# VideoMacPac_adapter.net
KiCad netlist of a schematic drawn in EAGLE
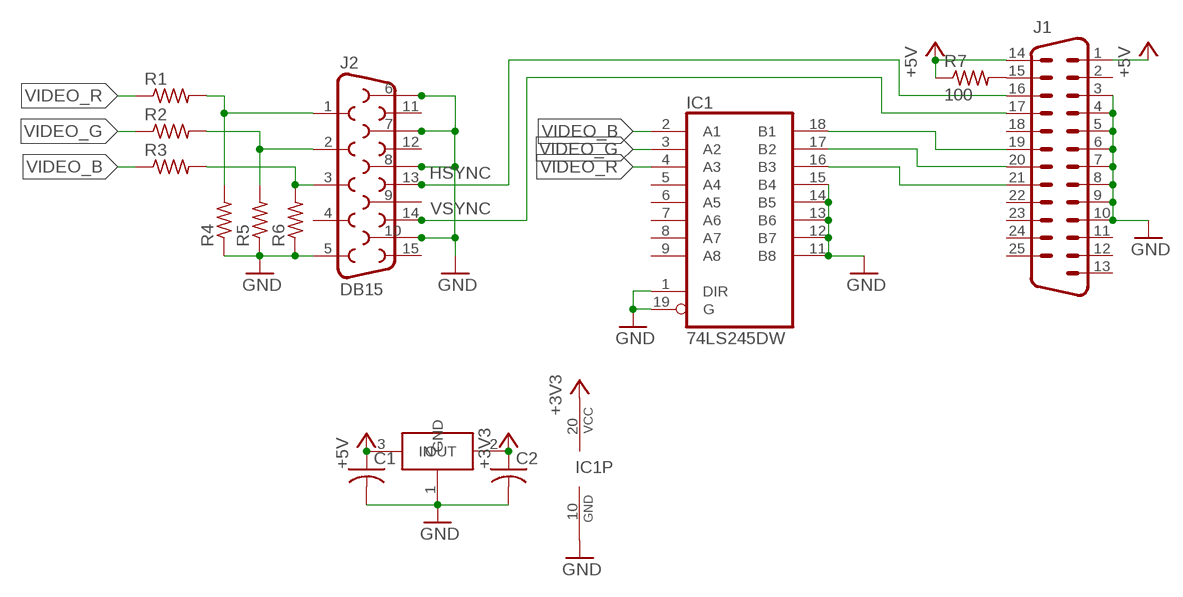
[diagram p0: schematic, sheet 1]

(export (version "E")
  (design (tool "Eeschema 10.0.6"))
  (components
    (comp (ref "C1")
      (value "C-USC0603")
      (footprint "eagle-import:C0603")
      (libsource (lib "eagle-import") (part "C-USC0603"))
    )
    (comp (ref "C2")
      (value "C-USC0603")
      (footprint "eagle-import:C0603")
      (libsource (lib "eagle-import") (part "C-USC0603"))
    )
    (comp (ref "IC1")
      (value "74LS245DW")
      (footprint "eagle-import:SO20W")
      (libsource (lib "eagle-import") (part "74245DWLS"))
    )
    (comp (ref "IC2")
      (value "MCP1700")
      (footprint "eagle-import:SOT23")
      (libsource (lib "eagle-import") (part "MCP1700"))
    )
    (comp (ref "J1")
      (value "DB25H")
      (footprint "eagle-import:M25H")
      (libsource (lib "eagle-import") (part "DB25H"))
    )
    (comp (ref "J2")
      (value "DB15")
      (footprint "eagle-import:DB15")
      (libsource (lib "eagle-import") (part "DB15"))
    )
    (comp (ref "R1")
      (value "R-US_R0603")
      (footprint "eagle-import:R0603")
      (libsource (lib "eagle-import") (part "R-US_R0603"))
    )
    (comp (ref "R2")
      (value "R-US_R0603")
      (footprint "eagle-import:R0603")
      (libsource (lib "eagle-import") (part "R-US_R0603"))
    )
    (comp (ref "R3")
      (value "R-US_R0603")
      (footprint "eagle-import:R0603")
      (libsource (lib "eagle-import") (part "R-US_R0603"))
    )
    (comp (ref "R4")
      (value "R-US_R0603")
      (footprint "eagle-import:R0603")
      (libsource (lib "eagle-import") (part "R-US_R0603"))
    )
    (comp (ref "R5")
      (value "R-US_R0603")
      (footprint "eagle-import:R0603")
      (libsource (lib "eagle-import") (part "R-US_R0603"))
    )
    (comp (ref "R6")
      (value "R-US_R0603")
      (footprint "eagle-import:R0603")
      (libsource (lib "eagle-import") (part "R-US_R0603"))
    )
    (comp (ref "R7")
      (value "100")
      (footprint "eagle-import:R0603")
      (libsource (lib "eagle-import") (part "R-US_R0603"))
    )
  )
  (nets
    (net (code "1") (name "+3V3") (class "Default")
      (node (ref "C2") (pin "1") (pinfunction "1_1") (pintype "passive"))
      (node (ref "IC1") (pin "20") (pinfunction "VCC_20") (pintype "power_in"))
      (node (ref "IC2") (pin "2") (pinfunction "OUT_2") (pintype "bidirectional"))
    )
    (net (code "2") (name "+5V") (class "Default")
      (node (ref "C1") (pin "1") (pinfunction "1_1") (pintype "passive"))
      (node (ref "IC2") (pin "3") (pinfunction "IN_3") (pintype "bidirectional"))
      (node (ref "J1") (pin "1") (pinfunction "1_1") (pintype "passive"))
      (node (ref "J1") (pin "14") (pinfunction "14_14") (pintype "passive"))
      (node (ref "R7") (pin "1") (pinfunction "1_1") (pintype "passive"))
    )
    (net (code "3") (name "/HSYNC") (class "Default")
      (node (ref "J1") (pin "16") (pinfunction "16_16") (pintype "passive"))
      (node (ref "J2") (pin "13") (pinfunction "13_13") (pintype "passive"))
    )
    (net (code "4") (name "/VSYNC") (class "Default")
      (node (ref "J1") (pin "17") (pinfunction "17_17") (pintype "passive"))
      (node (ref "J2") (pin "14") (pinfunction "14_14") (pintype "passive"))
    )
    (net (code "5") (name "GND") (class "Default")
      (node (ref "C1") (pin "2") (pinfunction "2_2") (pintype "passive"))
      (node (ref "C2") (pin "2") (pinfunction "2_2") (pintype "passive"))
      (node (ref "IC1") (pin "1") (pinfunction "DIR_1") (pintype "input"))
      (node (ref "IC1") (pin "10") (pinfunction "GND_10") (pintype "power_in"))
      (node (ref "IC1") (pin "11") (pinfunction "B8_11") (pintype "bidirectional"))
      (node (ref "IC1") (pin "12") (pinfunction "B7_12") (pintype "bidirectional"))
      (node (ref "IC1") (pin "13") (pinfunction "B6_13") (pintype "bidirectional"))
      (node (ref "IC1") (pin "14") (pinfunction "B5_14") (pintype "bidirectional"))
      (node (ref "IC1") (pin "15") (pinfunction "B4_15") (pintype "bidirectional"))
      (node (ref "IC1") (pin "19") (pinfunction "G_19") (pintype "input"))
      (node (ref "IC2") (pin "1") (pinfunction "GND_1") (pintype "bidirectional"))
      (node (ref "J1") (pin "10") (pinfunction "10_10") (pintype "passive"))
      (node (ref "J1") (pin "3") (pinfunction "3_3") (pintype "passive"))
      (node (ref "J1") (pin "4") (pinfunction "4_4") (pintype "passive"))
      (node (ref "J1") (pin "5") (pinfunction "5_5") (pintype "passive"))
      (node (ref "J1") (pin "6") (pinfunction "6_6") (pintype "passive"))
      (node (ref "J1") (pin "7") (pinfunction "7_7") (pintype "passive"))
      (node (ref "J1") (pin "8") (pinfunction "8_8") (pintype "passive"))
      (node (ref "J1") (pin "9") (pinfunction "9_9") (pintype "passive"))
      (node (ref "J2") (pin "10") (pinfunction "10_10") (pintype "passive"))
      (node (ref "J2") (pin "5") (pinfunction "5_5") (pintype "passive"))
      (node (ref "J2") (pin "6") (pinfunction "6_6") (pintype "passive"))
      (node (ref "J2") (pin "7") (pinfunction "7_7") (pintype "passive"))
      (node (ref "J2") (pin "8") (pinfunction "8_8") (pintype "passive"))
      (node (ref "R4") (pin "1") (pinfunction "1_1") (pintype "passive"))
      (node (ref "R5") (pin "1") (pinfunction "1_1") (pintype "passive"))
      (node (ref "R6") (pin "1") (pinfunction "1_1") (pintype "passive"))
    )
    (net (code "6") (name "Net-(IC1A-B1)") (class "Default")
      (node (ref "IC1") (pin "18") (pinfunction "B1_18") (pintype "bidirectional"))
      (node (ref "J1") (pin "19") (pinfunction "19_19") (pintype "passive"))
    )
    (net (code "7") (name "Net-(IC1A-B2)") (class "Default")
      (node (ref "IC1") (pin "17") (pinfunction "B2_17") (pintype "bidirectional"))
      (node (ref "J1") (pin "20") (pinfunction "20_20") (pintype "passive"))
    )
    (net (code "8") (name "Net-(IC1A-B3)") (class "Default")
      (node (ref "IC1") (pin "16") (pinfunction "B3_16") (pintype "bidirectional"))
      (node (ref "J1") (pin "21") (pinfunction "21_21") (pintype "passive"))
    )
    (net (code "9") (name "Net-(J1-Pad15)") (class "Default")
      (node (ref "J1") (pin "15") (pinfunction "15_15") (pintype "passive"))
      (node (ref "R7") (pin "2") (pinfunction "2_2") (pintype "passive"))
    )
    (net (code "10") (name "Net-(J2-Pad1)") (class "Default")
      (node (ref "J2") (pin "1") (pinfunction "1_1") (pintype "passive"))
      (node (ref "R1") (pin "2") (pinfunction "2_2") (pintype "passive"))
      (node (ref "R4") (pin "2") (pinfunction "2_2") (pintype "passive"))
    )
    (net (code "11") (name "Net-(J2-Pad2)") (class "Default")
      (node (ref "J2") (pin "2") (pinfunction "2_2") (pintype "passive"))
      (node (ref "R2") (pin "2") (pinfunction "2_2") (pintype "passive"))
      (node (ref "R5") (pin "2") (pinfunction "2_2") (pintype "passive"))
    )
    (net (code "12") (name "Net-(J2-Pad3)") (class "Default")
      (node (ref "J2") (pin "3") (pinfunction "3_3") (pintype "passive"))
      (node (ref "R3") (pin "2") (pinfunction "2_2") (pintype "passive"))
      (node (ref "R6") (pin "2") (pinfunction "2_2") (pintype "passive"))
    )
    (net (code "13") (name "VIDEO_B") (class "Default")
      (node (ref "IC1") (pin "2") (pinfunction "A1_2") (pintype "bidirectional"))
      (node (ref "R3") (pin "1") (pinfunction "1_1") (pintype "passive"))
    )
    (net (code "14") (name "VIDEO_G") (class "Default")
      (node (ref "IC1") (pin "3") (pinfunction "A2_3") (pintype "bidirectional"))
      (node (ref "R2") (pin "1") (pinfunction "1_1") (pintype "passive"))
    )
    (net (code "15") (name "VIDEO_R") (class "Default")
      (node (ref "IC1") (pin "4") (pinfunction "A3_4") (pintype "bidirectional"))
      (node (ref "R1") (pin "1") (pinfunction "1_1") (pintype "passive"))
    )
    (net (code "16") (name "unconnected-(IC1A-A4-Pad5)") (class "Default")
      (node (ref "IC1") (pin "5") (pinfunction "A4_5") (pintype "bidirectional"))
    )
    (net (code "17") (name "unconnected-(IC1A-A5-Pad6)") (class "Default")
      (node (ref "IC1") (pin "6") (pinfunction "A5_6") (pintype "bidirectional"))
    )
    (net (code "18") (name "unconnected-(IC1A-A6-Pad7)") (class "Default")
      (node (ref "IC1") (pin "7") (pinfunction "A6_7") (pintype "bidirectional"))
    )
    (net (code "19") (name "unconnected-(IC1A-A7-Pad8)") (class "Default")
      (node (ref "IC1") (pin "8") (pinfunction "A7_8") (pintype "bidirectional"))
    )
    (net (code "20") (name "unconnected-(IC1A-A8-Pad9)") (class "Default")
      (node (ref "IC1") (pin "9") (pinfunction "A8_9") (pintype "bidirectional"))
    )
    (net (code "21") (name "unconnected-(J1-Pad2)") (class "Default")
      (node (ref "J1") (pin "2") (pinfunction "2_2") (pintype "passive"))
    )
    (net (code "22") (name "unconnected-(J1-Pad11)") (class "Default")
      (node (ref "J1") (pin "11") (pinfunction "11_11") (pintype "passive"))
    )
    (net (code "23") (name "unconnected-(J1-Pad12)") (class "Default")
      (node (ref "J1") (pin "12") (pinfunction "12_12") (pintype "passive"))
    )
    (net (code "24") (name "unconnected-(J1-Pad13)") (class "Default")
      (node (ref "J1") (pin "13") (pinfunction "13_13") (pintype "passive"))
    )
    (net (code "25") (name "unconnected-(J1-Pad18)") (class "Default")
      (node (ref "J1") (pin "18") (pinfunction "18_18") (pintype "passive"))
    )
    (net (code "26") (name "unconnected-(J1-Pad22)") (class "Default")
      (node (ref "J1") (pin "22") (pinfunction "22_22") (pintype "passive"))
    )
    (net (code "27") (name "unconnected-(J1-Pad23)") (class "Default")
      (node (ref "J1") (pin "23") (pinfunction "23_23") (pintype "passive"))
    )
    (net (code "28") (name "unconnected-(J1-Pad24)") (class "Default")
      (node (ref "J1") (pin "24") (pinfunction "24_24") (pintype "passive"))
    )
    (net (code "29") (name "unconnected-(J1-Pad25)") (class "Default")
      (node (ref "J1") (pin "25") (pinfunction "25_25") (pintype "passive"))
    )
    (net (code "30") (name "unconnected-(J2-Pad4)") (class "Default")
      (node (ref "J2") (pin "4") (pinfunction "4_4") (pintype "passive"))
    )
    (net (code "31") (name "unconnected-(J2-Pad9)") (class "Default")
      (node (ref "J2") (pin "9") (pinfunction "9_9") (pintype "passive"))
    )
    (net (code "32") (name "unconnected-(J2-Pad11)") (class "Default")
      (node (ref "J2") (pin "11") (pinfunction "11_11") (pintype "passive"))
    )
    (net (code "33") (name "unconnected-(J2-Pad12)") (class "Default")
      (node (ref "J2") (pin "12") (pinfunction "12_12") (pintype "passive"))
    )
    (net (code "34") (name "unconnected-(J2-Pad15)") (class "Default")
      (node (ref "J2") (pin "15") (pinfunction "15_15") (pintype "passive"))
    )
  )
)
